# usb-helper.net
KiCad netlist of a schematic drawn in EAGLE
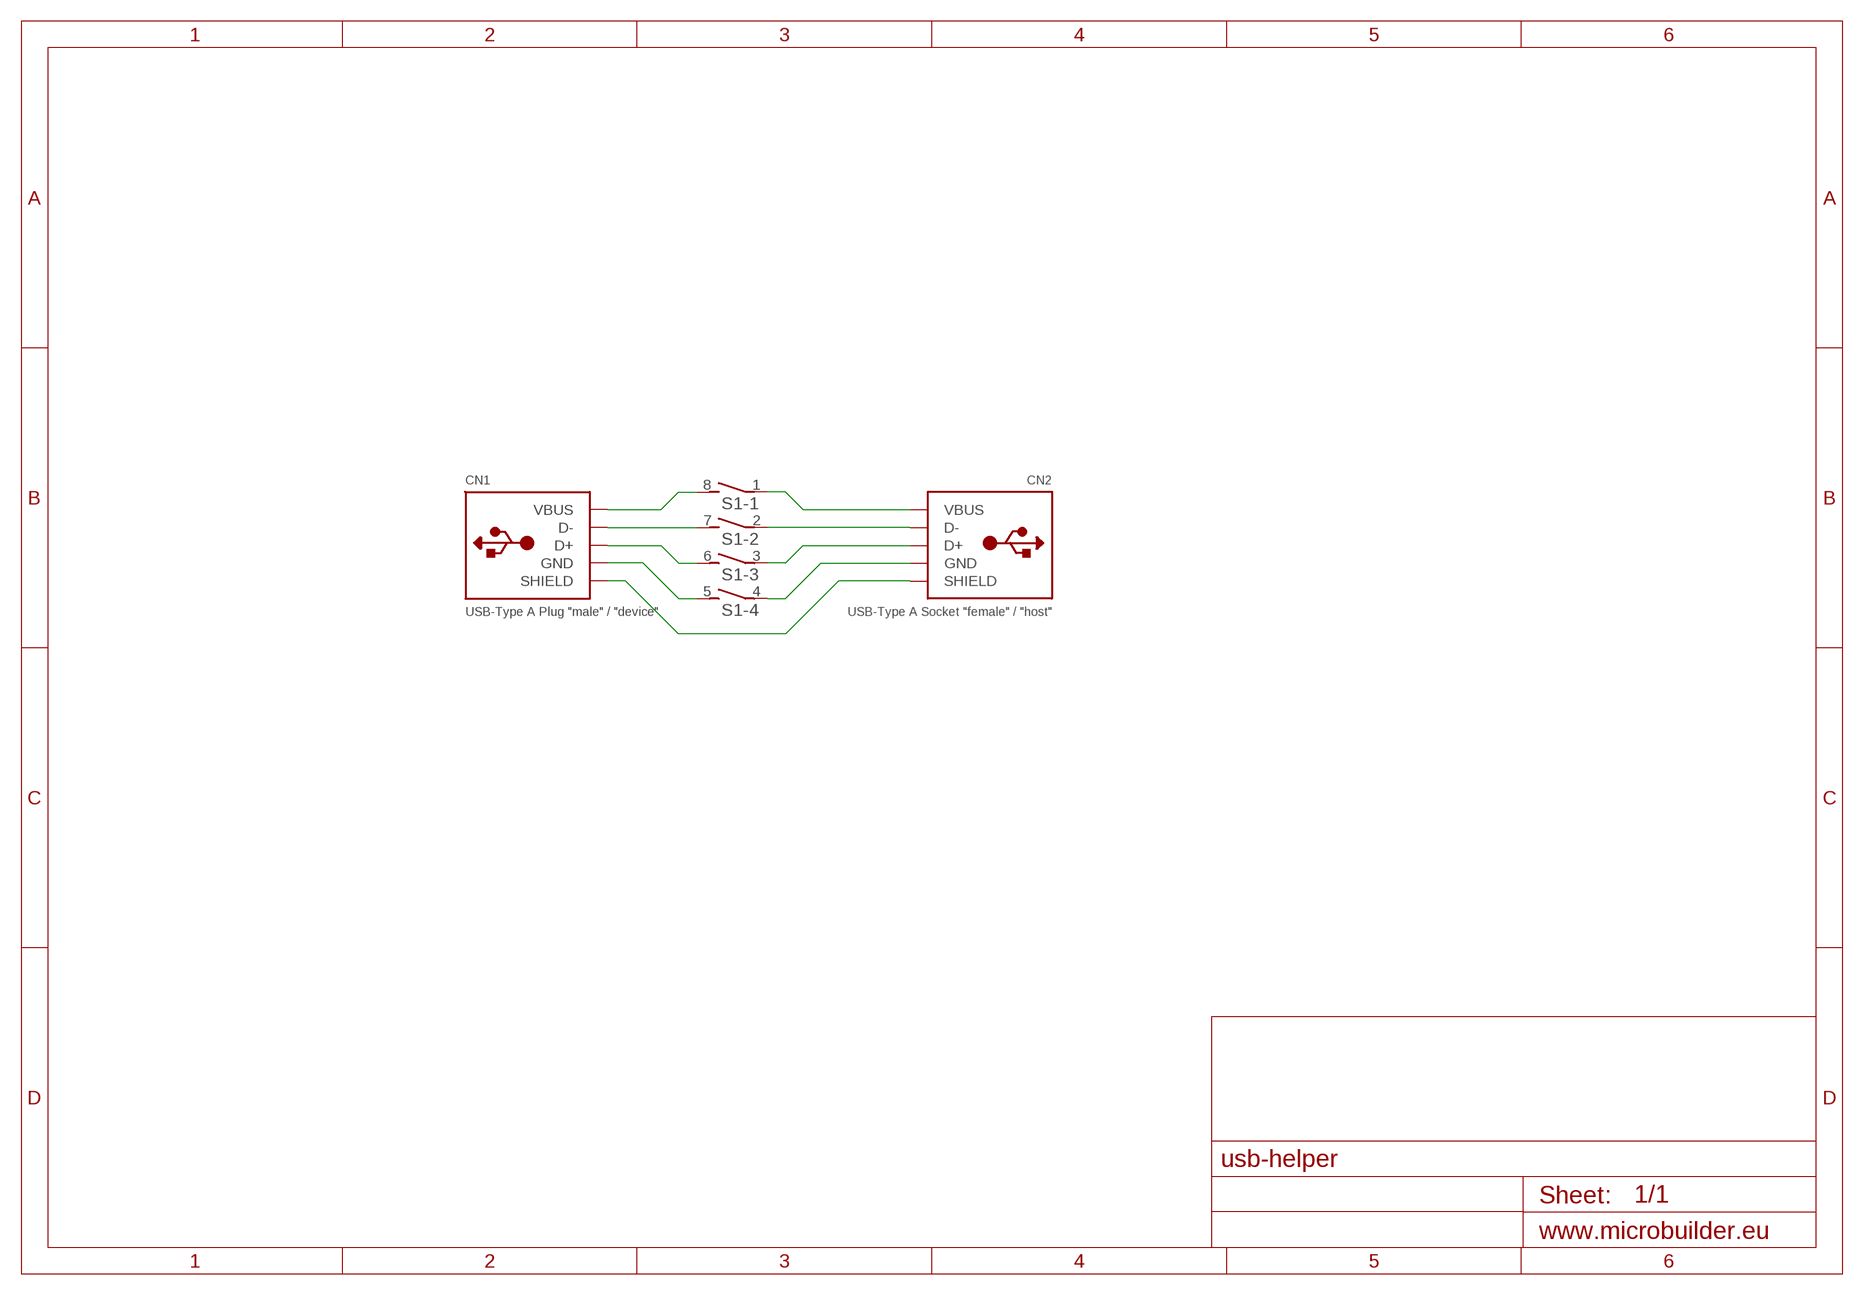
[diagram p0: schematic, sheet 1]

(export (version "E")
  (design (tool "Eeschema 10.0.6"))
  (components
    (comp (ref "CN1")
      (value "USB-Type A Plug \"male\" / \"device\"")
      (footprint "eagle-import:USB_PLUG_A_THT_AWF")
      (libsource (lib "eagle-import") (part "USB_TYPE_ATHT"))
    )
    (comp (ref "CN2")
      (value "USB-Type A Socket \"female\" / \"host\"")
      (footprint "eagle-import:USB_SOCKET_A_THT_AW")
      (libsource (lib "eagle-import") (part "USB_TYPE_A"))
    )
    (comp (ref "S1")
      (value "DIP04S_SECME")
      (footprint "eagle-import:DIP_04_SECME_THT")
      (libsource (lib "eagle-import") (part "DIP04S_SECME"))
    )
  )
  (nets
    (net (code "1") (name "Net-(CN1-SHIELD-PadSHIELD1)") (class "Default")
      (node (ref "CN1") (pin "SHIELD1") (pinfunction "SHIELD_SHIELD1") (pintype "passive"))
      (node (ref "CN1") (pin "SHIELD2") (pinfunction "SHIELD_SHIELD2") (pintype "passive"))
      (node (ref "CN2") (pin "S1") (pinfunction "SHIELD_S1") (pintype "passive"))
      (node (ref "CN2") (pin "S2") (pinfunction "SHIELD_S2") (pintype "passive"))
    )
    (net (code "2") (name "Net-(CN2-PadVBUS)") (class "Default")
      (node (ref "CN2") (pin "VBUS") (pinfunction "VBUS_VBUS") (pintype "power_in"))
      (node (ref "S1") (pin "1") (pinfunction "1_1") (pintype "passive"))
    )
    (net (code "3") (name "Net-(S1A-2)") (class "Default")
      (node (ref "CN1") (pin "VBUS") (pinfunction "VBUS_VBUS") (pintype "power_in"))
      (node (ref "S1") (pin "8") (pinfunction "2_8") (pintype "passive"))
    )
    (net (code "4") (name "Net-(S1B-1)") (class "Default")
      (node (ref "CN2") (pin "D-") (pinfunction "D-_D-") (pintype "bidirectional"))
      (node (ref "S1") (pin "2") (pinfunction "1_2") (pintype "passive"))
    )
    (net (code "5") (name "Net-(S1B-2)") (class "Default")
      (node (ref "CN1") (pin "D-") (pinfunction "D-_D-") (pintype "bidirectional"))
      (node (ref "S1") (pin "7") (pinfunction "2_7") (pintype "passive"))
    )
    (net (code "6") (name "Net-(S1C-1)") (class "Default")
      (node (ref "CN2") (pin "D+") (pinfunction "D+_D+") (pintype "bidirectional"))
      (node (ref "S1") (pin "3") (pinfunction "1_3") (pintype "passive"))
    )
    (net (code "7") (name "Net-(S1C-2)") (class "Default")
      (node (ref "CN1") (pin "D+") (pinfunction "D+_D+") (pintype "bidirectional"))
      (node (ref "S1") (pin "6") (pinfunction "2_6") (pintype "passive"))
    )
    (net (code "8") (name "Net-(S1D-1)") (class "Default")
      (node (ref "CN2") (pin "GND") (pinfunction "GND_GND") (pintype "power_in"))
      (node (ref "S1") (pin "4") (pinfunction "1_4") (pintype "passive"))
    )
    (net (code "9") (name "Net-(S1D-2)") (class "Default")
      (node (ref "CN1") (pin "GND") (pinfunction "GND_GND") (pintype "power_in"))
      (node (ref "S1") (pin "5") (pinfunction "2_5") (pintype "passive"))
    )
  )
)
